# TH8_LEDs.net
KiCad netlist of a schematic drawn in Altium Designer
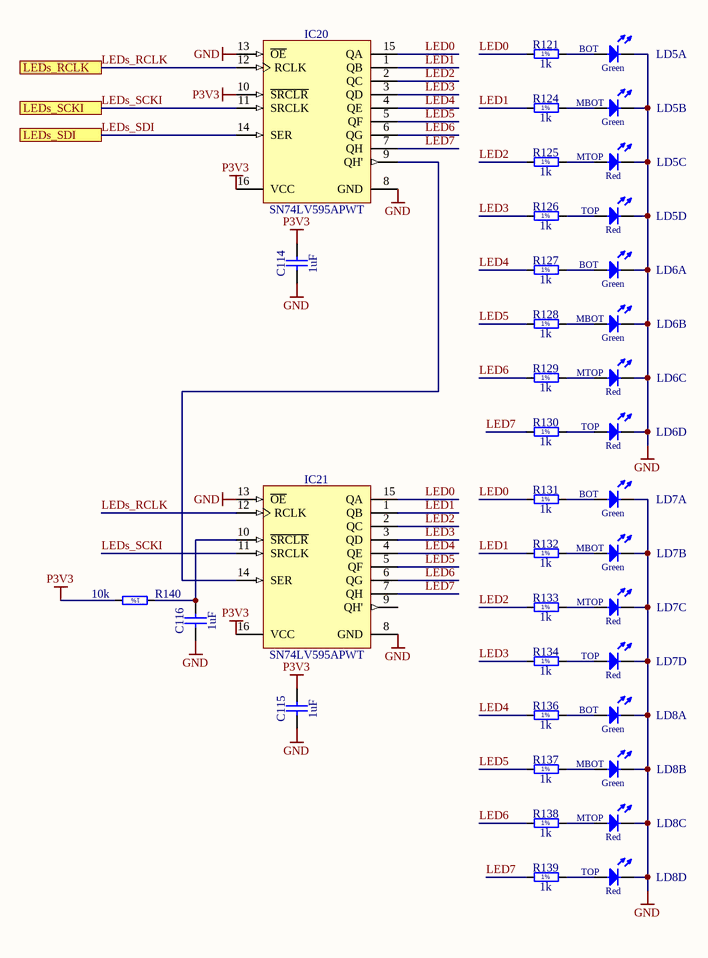
[diagram p0: TH8_LEDs.SchDoc]

(export (version "E")
  (design (tool "Eeschema 10.0.6"))
  (components
    (comp (ref "C114")
      (value "1uF")
      (footprint "CAPC1608X87N")
      (description "Non-polarised capacitor")
      (fields
        (field (name "PART NUMBER") "CC0603_1UF_25V_10%_X7R")
        (field (name "VOLTAGE") "25V")
        (field (name "AUTHOR") "CERN DEM JLC")
      )
      (libsource (lib "Capacitors") (part "Capacitor - non polarized"))
    )
    (comp (ref "C115")
      (value "1uF")
      (footprint "CAPC1608X87N")
      (description "Non-polarised capacitor")
      (fields
        (field (name "PART NUMBER") "CC0603_1UF_25V_10%_X7R")
        (field (name "VOLTAGE") "25V")
        (field (name "AUTHOR") "CERN DEM JLC")
      )
      (libsource (lib "Capacitors") (part "Capacitor - non polarized"))
    )
    (comp (ref "C116")
      (value "1uF")
      (footprint "CAPC1608X87N")
      (description "Non-polarised capacitor")
      (fields
        (field (name "PART NUMBER") "CC0603_1UF_25V_10%_X7R")
        (field (name "VOLTAGE") "25V")
        (field (name "AUTHOR") "CERN DEM JLC")
      )
      (libsource (lib "Capacitors") (part "Capacitor - non polarized"))
    )
    (comp (ref "IC20")
      (value "SN74LV595APWT")
      (footprint "SOP65P640X120-16N")
      (description "8-Bit Shift Register With 3-State Output Register")
      (fields (field (name "MANUFACTURER") "TEXAS INSTRUMENTS") (field (name "AUTHOR") "CERN DEM JLC"))
      (libsource (lib "ICs And Semiconductors") (part "74595"))
    )
    (comp (ref "IC21")
      (value "SN74LV595APWT")
      (footprint "SOP65P640X120-16N")
      (description "8-Bit Shift Register With 3-State Output Register")
      (fields (field (name "MANUFACTURER") "TEXAS INSTRUMENTS") (field (name "AUTHOR") "CERN DEM JLC"))
      (libsource (lib "ICs And Semiconductors") (part "74595"))
    )
    (comp (ref "LD5")
      (value "Green/Green/HeRed/HeRed")
      (footprint "LED_BIVAR_H485CHHGGDL")
      (description "LED x4 G-1C2A-BOT_G-3C4A_H-5C6A_H-7C8A-TOP")
      (fields
        (field (name "PART NUMBER") "LED_BIVAR_H485CHHGGDL")
        (field (name "MANUFACTURER") "BIVAR")
        (field (name "AUTHOR") "CERN DEM BC")
      )
      (libsource (lib "ICs And Semiconductors") (part "LED x4 G-1C2A-BOT_G-3C4A_H-5C6A_H-7C8A-TOP"))
    )
    (comp (ref "LD6")
      (value "Green/Green/HeRed/HeRed")
      (footprint "LED_BIVAR_H485CHHGGDL")
      (description "LED x4 G-1C2A-BOT_G-3C4A_H-5C6A_H-7C8A-TOP")
      (fields
        (field (name "PART NUMBER") "LED_BIVAR_H485CHHGGDL")
        (field (name "MANUFACTURER") "BIVAR")
        (field (name "AUTHOR") "CERN DEM BC")
      )
      (libsource (lib "ICs And Semiconductors") (part "LED x4 G-1C2A-BOT_G-3C4A_H-5C6A_H-7C8A-TOP"))
    )
    (comp (ref "LD7")
      (value "Green/Green/HeRed/HeRed")
      (footprint "LED_BIVAR_H485CHHGGDL")
      (description "LED x4 G-1C2A-BOT_G-3C4A_H-5C6A_H-7C8A-TOP")
      (fields
        (field (name "PART NUMBER") "LED_BIVAR_H485CHHGGDL")
        (field (name "MANUFACTURER") "BIVAR")
        (field (name "AUTHOR") "CERN DEM BC")
      )
      (libsource (lib "ICs And Semiconductors") (part "LED x4 G-1C2A-BOT_G-3C4A_H-5C6A_H-7C8A-TOP"))
    )
    (comp (ref "LD8")
      (value "Green/Green/HeRed/HeRed")
      (footprint "LED_BIVAR_H485CHHGGDL")
      (description "LED x4 G-1C2A-BOT_G-3C4A_H-5C6A_H-7C8A-TOP")
      (fields
        (field (name "PART NUMBER") "LED_BIVAR_H485CHHGGDL")
        (field (name "MANUFACTURER") "BIVAR")
        (field (name "AUTHOR") "CERN DEM BC")
      )
      (libsource (lib "ICs And Semiconductors") (part "LED x4 G-1C2A-BOT_G-3C4A_H-5C6A_H-7C8A-TOP"))
    )
    (comp (ref "R121")
      (value "1k")
      (footprint "RESC1005X40N")
      (description "Resistor - 1%")
      (fields
        (field (name "PART NUMBER") "R0402_1K_1%_0.0625W_100PPM")
        (field (name "POWER") "0.0625W")
        (field (name "AUTHOR") "CERN DEM JLC")
      )
      (libsource (lib "Resistors") (part "Resistor - 1%"))
    )
    (comp (ref "R124")
      (value "1k")
      (footprint "RESC1005X40N")
      (description "Resistor - 1%")
      (fields
        (field (name "PART NUMBER") "R0402_1K_1%_0.0625W_100PPM")
        (field (name "POWER") "0.0625W")
        (field (name "AUTHOR") "CERN DEM JLC")
      )
      (libsource (lib "Resistors") (part "Resistor - 1%"))
    )
    (comp (ref "R125")
      (value "1k")
      (footprint "RESC1005X40N")
      (description "Resistor - 1%")
      (fields
        (field (name "PART NUMBER") "R0402_1K_1%_0.0625W_100PPM")
        (field (name "POWER") "0.0625W")
        (field (name "AUTHOR") "CERN DEM JLC")
      )
      (libsource (lib "Resistors") (part "Resistor - 1%"))
    )
    (comp (ref "R126")
      (value "1k")
      (footprint "RESC1005X40N")
      (description "Resistor - 1%")
      (fields
        (field (name "PART NUMBER") "R0402_1K_1%_0.0625W_100PPM")
        (field (name "POWER") "0.0625W")
        (field (name "AUTHOR") "CERN DEM JLC")
      )
      (libsource (lib "Resistors") (part "Resistor - 1%"))
    )
    (comp (ref "R127")
      (value "1k")
      (footprint "RESC1005X40N")
      (description "Resistor - 1%")
      (fields
        (field (name "PART NUMBER") "R0402_1K_1%_0.0625W_100PPM")
        (field (name "POWER") "0.0625W")
        (field (name "AUTHOR") "CERN DEM JLC")
      )
      (libsource (lib "Resistors") (part "Resistor - 1%"))
    )
    (comp (ref "R128")
      (value "1k")
      (footprint "RESC1005X40N")
      (description "Resistor - 1%")
      (fields
        (field (name "PART NUMBER") "R0402_1K_1%_0.0625W_100PPM")
        (field (name "POWER") "0.0625W")
        (field (name "AUTHOR") "CERN DEM JLC")
      )
      (libsource (lib "Resistors") (part "Resistor - 1%"))
    )
    (comp (ref "R129")
      (value "1k")
      (footprint "RESC1005X40N")
      (description "Resistor - 1%")
      (fields
        (field (name "PART NUMBER") "R0402_1K_1%_0.0625W_100PPM")
        (field (name "POWER") "0.0625W")
        (field (name "AUTHOR") "CERN DEM JLC")
      )
      (libsource (lib "Resistors") (part "Resistor - 1%"))
    )
    (comp (ref "R130")
      (value "1k")
      (footprint "RESC1005X40N")
      (description "Resistor - 1%")
      (fields
        (field (name "PART NUMBER") "R0402_1K_1%_0.0625W_100PPM")
        (field (name "POWER") "0.0625W")
        (field (name "AUTHOR") "CERN DEM JLC")
      )
      (libsource (lib "Resistors") (part "Resistor - 1%"))
    )
    (comp (ref "R131")
      (value "1k")
      (footprint "RESC1005X40N")
      (description "Resistor - 1%")
      (fields
        (field (name "PART NUMBER") "R0402_1K_1%_0.0625W_100PPM")
        (field (name "POWER") "0.0625W")
        (field (name "AUTHOR") "CERN DEM JLC")
      )
      (libsource (lib "Resistors") (part "Resistor - 1%"))
    )
    (comp (ref "R132")
      (value "1k")
      (footprint "RESC1005X40N")
      (description "Resistor - 1%")
      (fields
        (field (name "PART NUMBER") "R0402_1K_1%_0.0625W_100PPM")
        (field (name "POWER") "0.0625W")
        (field (name "AUTHOR") "CERN DEM JLC")
      )
      (libsource (lib "Resistors") (part "Resistor - 1%"))
    )
    (comp (ref "R133")
      (value "1k")
      (footprint "RESC1005X40N")
      (description "Resistor - 1%")
      (fields
        (field (name "PART NUMBER") "R0402_1K_1%_0.0625W_100PPM")
        (field (name "POWER") "0.0625W")
        (field (name "AUTHOR") "CERN DEM JLC")
      )
      (libsource (lib "Resistors") (part "Resistor - 1%"))
    )
    (comp (ref "R134")
      (value "1k")
      (footprint "RESC1005X40N")
      (description "Resistor - 1%")
      (fields
        (field (name "PART NUMBER") "R0402_1K_1%_0.0625W_100PPM")
        (field (name "POWER") "0.0625W")
        (field (name "AUTHOR") "CERN DEM JLC")
      )
      (libsource (lib "Resistors") (part "Resistor - 1%"))
    )
    (comp (ref "R136")
      (value "1k")
      (footprint "RESC1005X40N")
      (description "Resistor - 1%")
      (fields
        (field (name "PART NUMBER") "R0402_1K_1%_0.0625W_100PPM")
        (field (name "POWER") "0.0625W")
        (field (name "AUTHOR") "CERN DEM JLC")
      )
      (libsource (lib "Resistors") (part "Resistor - 1%"))
    )
    (comp (ref "R137")
      (value "1k")
      (footprint "RESC1005X40N")
      (description "Resistor - 1%")
      (fields
        (field (name "PART NUMBER") "R0402_1K_1%_0.0625W_100PPM")
        (field (name "POWER") "0.0625W")
        (field (name "AUTHOR") "CERN DEM JLC")
      )
      (libsource (lib "Resistors") (part "Resistor - 1%"))
    )
    (comp (ref "R138")
      (value "1k")
      (footprint "RESC1005X40N")
      (description "Resistor - 1%")
      (fields
        (field (name "PART NUMBER") "R0402_1K_1%_0.0625W_100PPM")
        (field (name "POWER") "0.0625W")
        (field (name "AUTHOR") "CERN DEM JLC")
      )
      (libsource (lib "Resistors") (part "Resistor - 1%"))
    )
    (comp (ref "R139")
      (value "1k")
      (footprint "RESC1005X40N")
      (description "Resistor - 1%")
      (fields
        (field (name "PART NUMBER") "R0402_1K_1%_0.0625W_100PPM")
        (field (name "POWER") "0.0625W")
        (field (name "AUTHOR") "CERN DEM JLC")
      )
      (libsource (lib "Resistors") (part "Resistor - 1%"))
    )
    (comp (ref "R140")
      (value "10k")
      (footprint "RESC1005X40N")
      (description "Resistor - 1%")
      (fields
        (field (name "PART NUMBER") "R0402_10K_1%_0.0625W_100PPM")
        (field (name "POWER") "0.0625W")
        (field (name "AUTHOR") "CERN DEM JLC")
      )
      (libsource (lib "Resistors") (part "Resistor - 1%"))
    )
  )
  (nets
    (net (code "1") (name "/LED0") (class "Default")
      (node (ref "IC20") (pin "15") (pinfunction "QA_15") (pintype "tri_state"))
      (node (ref "IC21") (pin "15") (pinfunction "QA_15") (pintype "tri_state"))
      (node (ref "R121") (pin "1") (pinfunction "1_1") (pintype "passive"))
      (node (ref "R131") (pin "1") (pinfunction "1_1") (pintype "passive"))
    )
    (net (code "2") (name "/LED1") (class "Default")
      (node (ref "IC20") (pin "1") (pinfunction "QB_1") (pintype "tri_state"))
      (node (ref "IC21") (pin "1") (pinfunction "QB_1") (pintype "tri_state"))
      (node (ref "R124") (pin "1") (pinfunction "1_1") (pintype "passive"))
      (node (ref "R132") (pin "1") (pinfunction "1_1") (pintype "passive"))
    )
    (net (code "3") (name "/LED2") (class "Default")
      (node (ref "IC20") (pin "2") (pinfunction "QC_2") (pintype "tri_state"))
      (node (ref "IC21") (pin "2") (pinfunction "QC_2") (pintype "tri_state"))
      (node (ref "R125") (pin "1") (pinfunction "1_1") (pintype "passive"))
      (node (ref "R133") (pin "1") (pinfunction "1_1") (pintype "passive"))
    )
    (net (code "4") (name "/LED3") (class "Default")
      (node (ref "IC20") (pin "3") (pinfunction "QD_3") (pintype "tri_state"))
      (node (ref "IC21") (pin "3") (pinfunction "QD_3") (pintype "tri_state"))
      (node (ref "R126") (pin "1") (pinfunction "1_1") (pintype "passive"))
      (node (ref "R134") (pin "1") (pinfunction "1_1") (pintype "passive"))
    )
    (net (code "5") (name "/LED4") (class "Default")
      (node (ref "IC20") (pin "4") (pinfunction "QE_4") (pintype "tri_state"))
      (node (ref "IC21") (pin "4") (pinfunction "QE_4") (pintype "tri_state"))
      (node (ref "R127") (pin "1") (pinfunction "1_1") (pintype "passive"))
      (node (ref "R136") (pin "1") (pinfunction "1_1") (pintype "passive"))
    )
    (net (code "6") (name "/LED5") (class "Default")
      (node (ref "IC20") (pin "5") (pinfunction "QF_5") (pintype "tri_state"))
      (node (ref "IC21") (pin "5") (pinfunction "QF_5") (pintype "tri_state"))
      (node (ref "R128") (pin "1") (pinfunction "1_1") (pintype "passive"))
      (node (ref "R137") (pin "1") (pinfunction "1_1") (pintype "passive"))
    )
    (net (code "7") (name "/LED6") (class "Default")
      (node (ref "IC20") (pin "6") (pinfunction "QG_6") (pintype "tri_state"))
      (node (ref "IC21") (pin "6") (pinfunction "QG_6") (pintype "tri_state"))
      (node (ref "R129") (pin "1") (pinfunction "1_1") (pintype "passive"))
      (node (ref "R138") (pin "1") (pinfunction "1_1") (pintype "passive"))
    )
    (net (code "8") (name "/LED7") (class "Default")
      (node (ref "IC20") (pin "7") (pinfunction "QH_7") (pintype "tri_state"))
      (node (ref "IC21") (pin "7") (pinfunction "QH_7") (pintype "tri_state"))
      (node (ref "R130") (pin "1") (pinfunction "1_1") (pintype "passive"))
      (node (ref "R139") (pin "1") (pinfunction "1_1") (pintype "passive"))
    )
    (net (code "9") (name "/LEDs_RCLK") (class "Default")
      (node (ref "IC20") (pin "12") (pinfunction "RCLK_12") (pintype "input"))
      (node (ref "IC21") (pin "12") (pinfunction "RCLK_12") (pintype "input"))
    )
    (net (code "10") (name "/LEDs_SCKI") (class "Default")
      (node (ref "IC20") (pin "11") (pinfunction "SRCLK_11") (pintype "input"))
      (node (ref "IC21") (pin "11") (pinfunction "SRCLK_11") (pintype "input"))
    )
    (net (code "11") (name "/LEDs_SDI") (class "Default")
      (node (ref "IC20") (pin "14") (pinfunction "SER_14") (pintype "input"))
    )
    (net (code "12") (name "GND") (class "Default")
      (node (ref "C114") (pin "1") (pinfunction "1_1") (pintype "passive"))
      (node (ref "C115") (pin "1") (pinfunction "1_1") (pintype "passive"))
      (node (ref "C116") (pin "1") (pinfunction "1_1") (pintype "passive"))
      (node (ref "IC20") (pin "13") (pinfunction "~{OE}_13") (pintype "input"))
      (node (ref "IC20") (pin "8") (pinfunction "GND_8") (pintype "power_in"))
      (node (ref "IC21") (pin "13") (pinfunction "~{OE}_13") (pintype "input"))
      (node (ref "IC21") (pin "8") (pinfunction "GND_8") (pintype "power_in"))
      (node (ref "LD5") (pin "1") (pinfunction "C_1") (pintype "passive"))
      (node (ref "LD5") (pin "3") (pinfunction "C_3") (pintype "passive"))
      (node (ref "LD5") (pin "5") (pinfunction "C_5") (pintype "passive"))
      (node (ref "LD5") (pin "7") (pinfunction "C_7") (pintype "passive"))
      (node (ref "LD6") (pin "1") (pinfunction "C_1") (pintype "passive"))
      (node (ref "LD6") (pin "3") (pinfunction "C_3") (pintype "passive"))
      (node (ref "LD6") (pin "5") (pinfunction "C_5") (pintype "passive"))
      (node (ref "LD6") (pin "7") (pinfunction "C_7") (pintype "passive"))
      (node (ref "LD7") (pin "1") (pinfunction "C_1") (pintype "passive"))
      (node (ref "LD7") (pin "3") (pinfunction "C_3") (pintype "passive"))
      (node (ref "LD7") (pin "5") (pinfunction "C_5") (pintype "passive"))
      (node (ref "LD7") (pin "7") (pinfunction "C_7") (pintype "passive"))
      (node (ref "LD8") (pin "1") (pinfunction "C_1") (pintype "passive"))
      (node (ref "LD8") (pin "3") (pinfunction "C_3") (pintype "passive"))
      (node (ref "LD8") (pin "5") (pinfunction "C_5") (pintype "passive"))
      (node (ref "LD8") (pin "7") (pinfunction "C_7") (pintype "passive"))
    )
    (net (code "13") (name "Net-(IC20-QH')") (class "Default")
      (node (ref "IC20") (pin "9") (pinfunction "QH'_9") (pintype "output"))
      (node (ref "IC21") (pin "14") (pinfunction "SER_14") (pintype "input"))
    )
    (net (code "14") (name "Net-(IC21-~{SRCLR})") (class "Default")
      (node (ref "C116") (pin "2") (pinfunction "2_2") (pintype "passive"))
      (node (ref "IC21") (pin "10") (pinfunction "~{SRCLR}_10") (pintype "input"))
      (node (ref "R140") (pin "1") (pinfunction "1_1") (pintype "passive"))
    )
    (net (code "15") (name "Net-(LD5A-A)") (class "Default")
      (node (ref "LD5") (pin "2") (pinfunction "A_2") (pintype "passive"))
      (node (ref "R121") (pin "2") (pinfunction "2_2") (pintype "passive"))
    )
    (net (code "16") (name "Net-(LD5B-A)") (class "Default")
      (node (ref "LD5") (pin "4") (pinfunction "A_4") (pintype "passive"))
      (node (ref "R124") (pin "2") (pinfunction "2_2") (pintype "passive"))
    )
    (net (code "17") (name "Net-(LD5C-A)") (class "Default")
      (node (ref "LD5") (pin "6") (pinfunction "A_6") (pintype "passive"))
      (node (ref "R125") (pin "2") (pinfunction "2_2") (pintype "passive"))
    )
    (net (code "18") (name "Net-(LD5D-A)") (class "Default")
      (node (ref "LD5") (pin "8") (pinfunction "A_8") (pintype "passive"))
      (node (ref "R126") (pin "2") (pinfunction "2_2") (pintype "passive"))
    )
    (net (code "19") (name "Net-(LD6A-A)") (class "Default")
      (node (ref "LD6") (pin "2") (pinfunction "A_2") (pintype "passive"))
      (node (ref "R127") (pin "2") (pinfunction "2_2") (pintype "passive"))
    )
    (net (code "20") (name "Net-(LD6B-A)") (class "Default")
      (node (ref "LD6") (pin "4") (pinfunction "A_4") (pintype "passive"))
      (node (ref "R128") (pin "2") (pinfunction "2_2") (pintype "passive"))
    )
    (net (code "21") (name "Net-(LD6C-A)") (class "Default")
      (node (ref "LD6") (pin "6") (pinfunction "A_6") (pintype "passive"))
      (node (ref "R129") (pin "2") (pinfunction "2_2") (pintype "passive"))
    )
    (net (code "22") (name "Net-(LD6D-A)") (class "Default")
      (node (ref "LD6") (pin "8") (pinfunction "A_8") (pintype "passive"))
      (node (ref "R130") (pin "2") (pinfunction "2_2") (pintype "passive"))
    )
    (net (code "23") (name "Net-(LD7A-A)") (class "Default")
      (node (ref "LD7") (pin "2") (pinfunction "A_2") (pintype "passive"))
      (node (ref "R131") (pin "2") (pinfunction "2_2") (pintype "passive"))
    )
    (net (code "24") (name "Net-(LD7B-A)") (class "Default")
      (node (ref "LD7") (pin "4") (pinfunction "A_4") (pintype "passive"))
      (node (ref "R132") (pin "2") (pinfunction "2_2") (pintype "passive"))
    )
    (net (code "25") (name "Net-(LD7C-A)") (class "Default")
      (node (ref "LD7") (pin "6") (pinfunction "A_6") (pintype "passive"))
      (node (ref "R133") (pin "2") (pinfunction "2_2") (pintype "passive"))
    )
    (net (code "26") (name "Net-(LD7D-A)") (class "Default")
      (node (ref "LD7") (pin "8") (pinfunction "A_8") (pintype "passive"))
      (node (ref "R134") (pin "2") (pinfunction "2_2") (pintype "passive"))
    )
    (net (code "27") (name "Net-(LD8A-A)") (class "Default")
      (node (ref "LD8") (pin "2") (pinfunction "A_2") (pintype "passive"))
      (node (ref "R136") (pin "2") (pinfunction "2_2") (pintype "passive"))
    )
    (net (code "28") (name "Net-(LD8B-A)") (class "Default")
      (node (ref "LD8") (pin "4") (pinfunction "A_4") (pintype "passive"))
      (node (ref "R137") (pin "2") (pinfunction "2_2") (pintype "passive"))
    )
    (net (code "29") (name "Net-(LD8C-A)") (class "Default")
      (node (ref "LD8") (pin "6") (pinfunction "A_6") (pintype "passive"))
      (node (ref "R138") (pin "2") (pinfunction "2_2") (pintype "passive"))
    )
    (net (code "30") (name "Net-(LD8D-A)") (class "Default")
      (node (ref "LD8") (pin "8") (pinfunction "A_8") (pintype "passive"))
      (node (ref "R139") (pin "2") (pinfunction "2_2") (pintype "passive"))
    )
    (net (code "31") (name "P3V3") (class "Default")
      (node (ref "C114") (pin "2") (pinfunction "2_2") (pintype "passive"))
      (node (ref "C115") (pin "2") (pinfunction "2_2") (pintype "passive"))
      (node (ref "IC20") (pin "10") (pinfunction "~{SRCLR}_10") (pintype "input"))
      (node (ref "IC20") (pin "16") (pinfunction "VCC_16") (pintype "power_in"))
      (node (ref "IC21") (pin "16") (pinfunction "VCC_16") (pintype "power_in"))
      (node (ref "R140") (pin "2") (pinfunction "2_2") (pintype "passive"))
    )
    (net (code "32") (name "unconnected-(IC21-QH'-Pad9)") (class "Default")
      (node (ref "IC21") (pin "9") (pinfunction "QH'_9") (pintype "output"))
    )
  )
)
